# rc_rx_3_3V_with_gyro_iface_and_rear_H-br.net
KiCad netlist of a schematic drawn in EAGLE
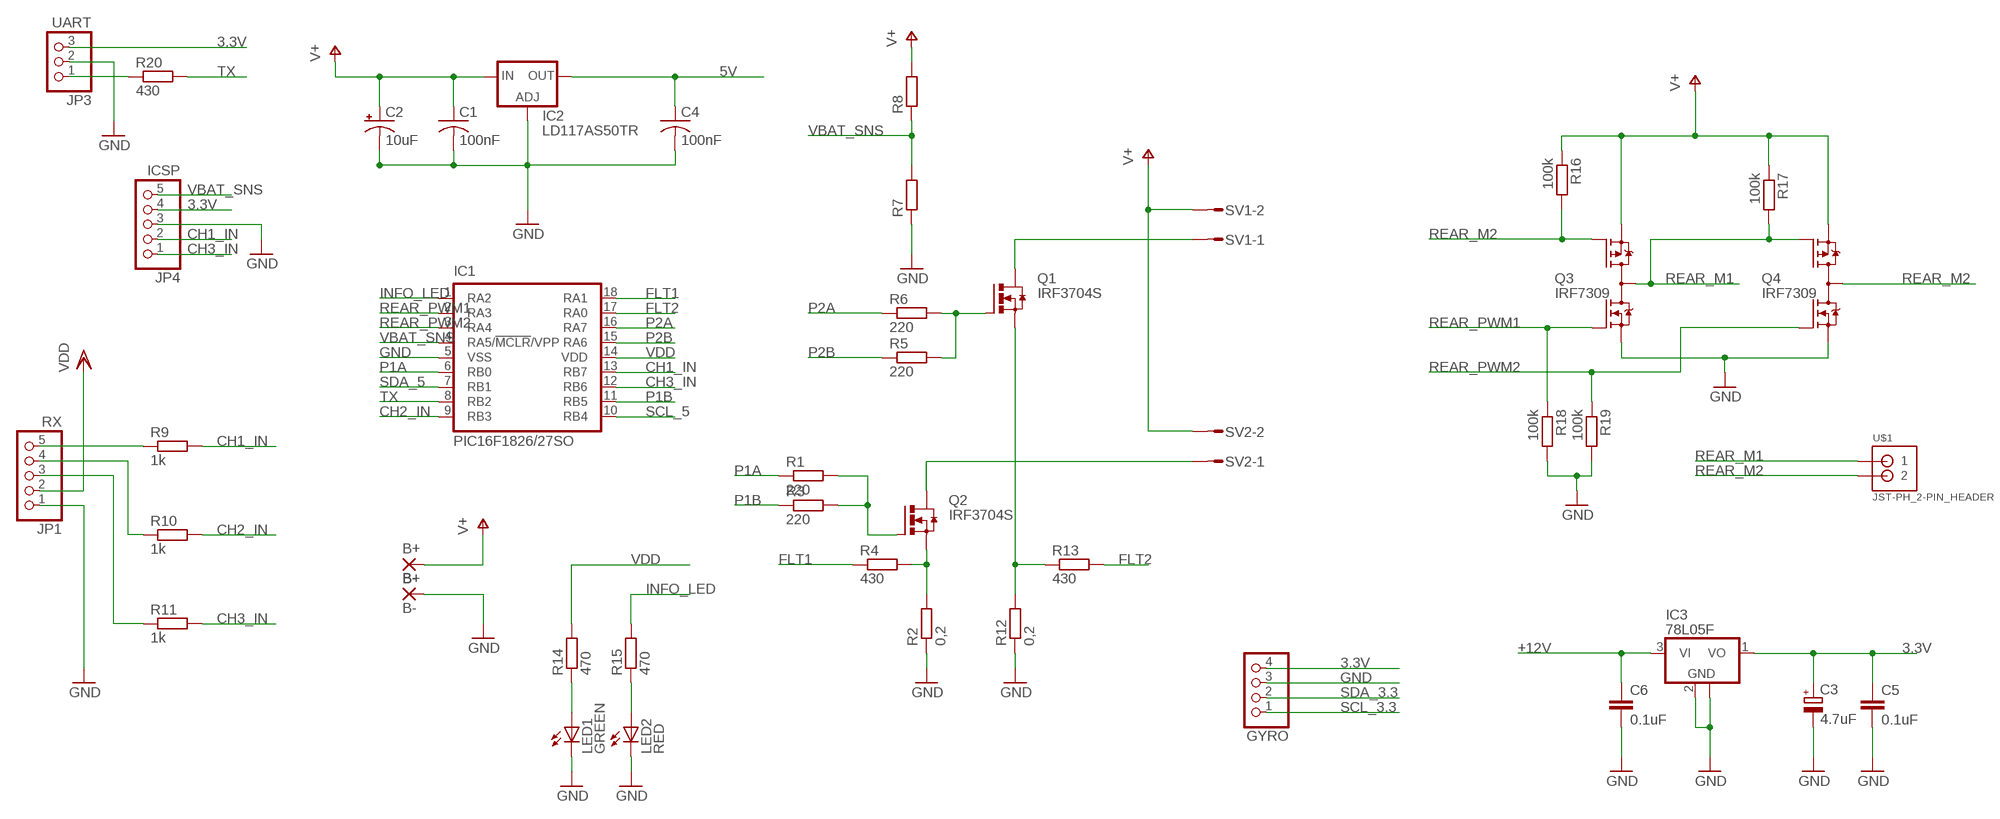
[diagram p0: schematic, sheet 1]

(export (version "E")
  (design (tool "Eeschema 10.0.6"))
  (components
    (comp (ref "B+")
      (value "B+")
      (footprint "eagle-import:3,81_1,4")
      (libsource (lib "eagle-import") (part "3,81/1,4"))
    )
    (comp (ref "B-")
      (value "B-")
      (footprint "eagle-import:3,81_1,4")
      (libsource (lib "eagle-import") (part "3,81/1,4"))
    )
    (comp (ref "C1")
      (value "100nF")
      (footprint "eagle-import:C0805")
      (libsource (lib "eagle-import") (part "C-USC0805"))
    )
    (comp (ref "C2")
      (value "10uF")
      (footprint "eagle-import:E3,5-8")
      (libsource (lib "eagle-import") (part "CPOL-USE3.5-8"))
    )
    (comp (ref "C3")
      (value "4.7uF")
      (footprint "eagle-import:E1,8-4")
      (libsource (lib "eagle-import") (part "CPOL-EUE1.8-4"))
    )
    (comp (ref "C4")
      (value "100nF")
      (footprint "eagle-import:C0805")
      (libsource (lib "eagle-import") (part "C-USC0805"))
    )
    (comp (ref "C5")
      (value "0.1uF")
      (footprint "eagle-import:C0805")
      (libsource (lib "eagle-import") (part "C-EUC0805"))
    )
    (comp (ref "C6")
      (value "0.1uF")
      (footprint "eagle-import:C0805")
      (libsource (lib "eagle-import") (part "C-EUC0805"))
    )
    (comp (ref "GYRO")
      (value "PINHD-1X4")
      (footprint "eagle-import:1X04")
      (libsource (lib "eagle-import") (part "PINHD-1X4"))
    )
    (comp (ref "IC1")
      (value "PIC16F1826/27SO")
      (footprint "eagle-import:SO-18W")
      (libsource (lib "eagle-import") (part "PIC16F1826/27SO"))
    )
    (comp (ref "IC2")
      (value "LD117AS50TR")
      (footprint "eagle-import:SOT223")
      (libsource (lib "eagle-import") (part "LD117A?S50TR"))
    )
    (comp (ref "IC3")
      (value "78L05F")
      (footprint "eagle-import:SOT89")
      (libsource (lib "eagle-import") (part "78LF05"))
    )
    (comp (ref "JP1")
      (value "RX")
      (footprint "eagle-import:1X05")
      (libsource (lib "eagle-import") (part "PINHD-1X5"))
    )
    (comp (ref "JP3")
      (value "UART")
      (footprint "eagle-import:1X03")
      (libsource (lib "eagle-import") (part "PINHD-1X3"))
    )
    (comp (ref "JP4")
      (value "ICSP")
      (footprint "eagle-import:1X05")
      (libsource (lib "eagle-import") (part "PINHD-1X5"))
    )
    (comp (ref "LED1")
      (value "GREEN")
      (footprint "eagle-import:CHIP-LED0603")
      (libsource (lib "eagle-import") (part "LEDCHIP-LED0603"))
    )
    (comp (ref "LED2")
      (value "RED")
      (footprint "eagle-import:CHIP-LED0603")
      (libsource (lib "eagle-import") (part "LEDCHIP-LED0603"))
    )
    (comp (ref "Q1")
      (value "IRF3704S")
      (footprint "eagle-import:D2PACK")
      (libsource (lib "eagle-import") (part "IRF3704S"))
    )
    (comp (ref "Q2")
      (value "IRF3704S")
      (footprint "eagle-import:D2PACK")
      (libsource (lib "eagle-import") (part "IRF3704S"))
    )
    (comp (ref "Q3")
      (value "IRF7309")
      (footprint "eagle-import:SO08-IRF")
      (libsource (lib "eagle-import") (part "IRF7389"))
    )
    (comp (ref "Q4")
      (value "IRF7309")
      (footprint "eagle-import:SO08-IRF")
      (libsource (lib "eagle-import") (part "IRF7389"))
    )
    (comp (ref "R1")
      (value "220")
      (footprint "eagle-import:M0805")
      (libsource (lib "eagle-import") (part "R-EU_M0805"))
    )
    (comp (ref "R2")
      (value "0,2")
      (footprint "eagle-import:M0805")
      (libsource (lib "eagle-import") (part "R-EU_M0805"))
    )
    (comp (ref "R3")
      (value "220")
      (footprint "eagle-import:M0805")
      (libsource (lib "eagle-import") (part "R-EU_M0805"))
    )
    (comp (ref "R4")
      (value "430")
      (footprint "eagle-import:M0805")
      (libsource (lib "eagle-import") (part "R-EU_M0805"))
    )
    (comp (ref "R5")
      (value "220")
      (footprint "eagle-import:R0805")
      (libsource (lib "eagle-import") (part "R-EU_R0805"))
    )
    (comp (ref "R6")
      (value "220")
      (footprint "eagle-import:M0805")
      (libsource (lib "eagle-import") (part "R-EU_M0805"))
    )
    (comp (ref "R7")
      (value "R-EU_R0805")
      (footprint "eagle-import:R0805")
      (libsource (lib "eagle-import") (part "R-EU_R0805"))
    )
    (comp (ref "R8")
      (value "R-EU_R0805")
      (footprint "eagle-import:R0805")
      (libsource (lib "eagle-import") (part "R-EU_R0805"))
    )
    (comp (ref "R9")
      (value "1k")
      (footprint "eagle-import:M0805")
      (libsource (lib "eagle-import") (part "R-EU_M0805"))
    )
    (comp (ref "R10")
      (value "1k")
      (footprint "eagle-import:M0805")
      (libsource (lib "eagle-import") (part "R-EU_M0805"))
    )
    (comp (ref "R11")
      (value "1k")
      (footprint "eagle-import:M0805")
      (libsource (lib "eagle-import") (part "R-EU_M0805"))
    )
    (comp (ref "R12")
      (value "0,2")
      (footprint "eagle-import:M0805")
      (libsource (lib "eagle-import") (part "R-EU_M0805"))
    )
    (comp (ref "R13")
      (value "430")
      (footprint "eagle-import:M0805")
      (libsource (lib "eagle-import") (part "R-EU_M0805"))
    )
    (comp (ref "R14")
      (value "470")
      (footprint "eagle-import:M0805")
      (libsource (lib "eagle-import") (part "R-EU_M0805"))
    )
    (comp (ref "R15")
      (value "470")
      (footprint "eagle-import:M0805")
      (libsource (lib "eagle-import") (part "R-EU_M0805"))
    )
    (comp (ref "R16")
      (value "100k")
      (footprint "eagle-import:M0805")
      (libsource (lib "eagle-import") (part "R-EU_M0805"))
    )
    (comp (ref "R17")
      (value "100k")
      (footprint "eagle-import:M0805")
      (libsource (lib "eagle-import") (part "R-EU_M0805"))
    )
    (comp (ref "R18")
      (value "100k")
      (footprint "eagle-import:M0805")
      (libsource (lib "eagle-import") (part "R-EU_M0805"))
    )
    (comp (ref "R19")
      (value "100k")
      (footprint "eagle-import:M0805")
      (libsource (lib "eagle-import") (part "R-EU_M0805"))
    )
    (comp (ref "R20")
      (value "430")
      (footprint "eagle-import:M0805")
      (libsource (lib "eagle-import") (part "R-EU_M0805"))
    )
    (comp (ref "SV1")
      (value "S02P")
      (footprint "eagle-import:S02P")
      (libsource (lib "eagle-import") (part "S02P"))
    )
    (comp (ref "SV2")
      (value "S02P")
      (footprint "eagle-import:S02P")
      (libsource (lib "eagle-import") (part "S02P"))
    )
    (comp (ref "U$1")
      (value "JST-PH_2-PIN_HEADER")
      (footprint "eagle-import:JST_B2B-PH_HEADER")
      (libsource (lib "eagle-import") (part "JST-PH_2-PIN_HEADER"))
    )
  )
  (nets
    (net (code "1") (name "/+12V") (class "Default")
      (node (ref "C6") (pin "1") (pinfunction "1_1") (pintype "passive"))
      (node (ref "IC3") (pin "3") (pinfunction "VI_3") (pintype "input"))
    )
    (net (code "2") (name "/3.3V") (class "Default")
      (node (ref "C3") (pin "+") (pinfunction "+_+") (pintype "passive"))
      (node (ref "C5") (pin "1") (pinfunction "1_1") (pintype "passive"))
      (node (ref "GYRO") (pin "4") (pinfunction "4_4") (pintype "passive"))
      (node (ref "IC3") (pin "1") (pinfunction "VO_1") (pintype "passive"))
      (node (ref "JP3") (pin "3") (pinfunction "3_3") (pintype "passive"))
      (node (ref "JP4") (pin "4") (pinfunction "4_4") (pintype "passive"))
    )
    (net (code "3") (name "/5V") (class "Default")
      (node (ref "C4") (pin "1") (pinfunction "1_1") (pintype "passive"))
      (node (ref "IC2") (pin "4") (pinfunction "OUT_4") (pintype "passive"))
    )
    (net (code "4") (name "/CH1_IN") (class "Default")
      (node (ref "IC1") (pin "13") (pinfunction "RB7_13") (pintype "bidirectional"))
      (node (ref "JP4") (pin "2") (pinfunction "2_2") (pintype "passive"))
      (node (ref "R9") (pin "2") (pinfunction "2_2") (pintype "passive"))
    )
    (net (code "5") (name "/CH2_IN") (class "Default")
      (node (ref "IC1") (pin "9") (pinfunction "RB3_9") (pintype "bidirectional"))
      (node (ref "R10") (pin "2") (pinfunction "2_2") (pintype "passive"))
    )
    (net (code "6") (name "/CH3_IN") (class "Default")
      (node (ref "IC1") (pin "12") (pinfunction "RB6_12") (pintype "bidirectional"))
      (node (ref "JP4") (pin "1") (pinfunction "1_1") (pintype "passive"))
      (node (ref "R11") (pin "2") (pinfunction "2_2") (pintype "passive"))
    )
    (net (code "7") (name "/FLT1") (class "Default")
      (node (ref "IC1") (pin "18") (pinfunction "RA1_18") (pintype "bidirectional"))
      (node (ref "R4") (pin "1") (pinfunction "1_1") (pintype "passive"))
    )
    (net (code "8") (name "/FLT2") (class "Default")
      (node (ref "IC1") (pin "17") (pinfunction "RA0_17") (pintype "bidirectional"))
      (node (ref "R13") (pin "2") (pinfunction "2_2") (pintype "passive"))
    )
    (net (code "9") (name "/INFO_LED") (class "Default")
      (node (ref "IC1") (pin "1") (pinfunction "RA2_1") (pintype "bidirectional"))
      (node (ref "R15") (pin "2") (pinfunction "2_2") (pintype "passive"))
    )
    (net (code "10") (name "/P1A") (class "Default")
      (node (ref "IC1") (pin "6") (pinfunction "RB0_6") (pintype "bidirectional"))
      (node (ref "R1") (pin "1") (pinfunction "1_1") (pintype "passive"))
    )
    (net (code "11") (name "/P1B") (class "Default")
      (node (ref "IC1") (pin "11") (pinfunction "RB5_11") (pintype "bidirectional"))
      (node (ref "R3") (pin "1") (pinfunction "1_1") (pintype "passive"))
    )
    (net (code "12") (name "/P2A") (class "Default")
      (node (ref "IC1") (pin "16") (pinfunction "RA7_16") (pintype "bidirectional"))
      (node (ref "R6") (pin "1") (pinfunction "1_1") (pintype "passive"))
    )
    (net (code "13") (name "/P2B") (class "Default")
      (node (ref "IC1") (pin "15") (pinfunction "RA6_15") (pintype "bidirectional"))
      (node (ref "R5") (pin "1") (pinfunction "1_1") (pintype "passive"))
    )
    (net (code "14") (name "/REAR_M1") (class "Default")
      (node (ref "Q3") (pin "5") (pinfunction "D_5") (pintype "passive"))
      (node (ref "Q3") (pin "6") (pinfunction "D_6") (pintype "passive"))
      (node (ref "Q3") (pin "7") (pinfunction "D_7") (pintype "passive"))
      (node (ref "Q3") (pin "8") (pinfunction "D_8") (pintype "passive"))
      (node (ref "Q4") (pin "4") (pinfunction "P-G_4") (pintype "passive"))
      (node (ref "R17") (pin "2") (pinfunction "2_2") (pintype "passive"))
      (node (ref "U$1") (pin "P1") (pinfunction "1_P1") (pintype "bidirectional"))
    )
    (net (code "15") (name "/REAR_M2") (class "Default")
      (node (ref "Q3") (pin "4") (pinfunction "P-G_4") (pintype "passive"))
      (node (ref "Q4") (pin "5") (pinfunction "D_5") (pintype "passive"))
      (node (ref "Q4") (pin "6") (pinfunction "D_6") (pintype "passive"))
      (node (ref "Q4") (pin "7") (pinfunction "D_7") (pintype "passive"))
      (node (ref "Q4") (pin "8") (pinfunction "D_8") (pintype "passive"))
      (node (ref "R16") (pin "2") (pinfunction "2_2") (pintype "passive"))
      (node (ref "U$1") (pin "P2") (pinfunction "2_P2") (pintype "bidirectional"))
    )
    (net (code "16") (name "/REAR_PWM1") (class "Default")
      (node (ref "IC1") (pin "2") (pinfunction "RA3_2") (pintype "bidirectional"))
      (node (ref "Q3") (pin "2") (pinfunction "N-G_2") (pintype "passive"))
      (node (ref "R18") (pin "1") (pinfunction "1_1") (pintype "passive"))
    )
    (net (code "17") (name "/REAR_PWM2") (class "Default")
      (node (ref "IC1") (pin "3") (pinfunction "RA4_3") (pintype "bidirectional"))
      (node (ref "Q4") (pin "2") (pinfunction "N-G_2") (pintype "passive"))
      (node (ref "R19") (pin "1") (pinfunction "1_1") (pintype "passive"))
    )
    (net (code "18") (name "/SCL_3.3") (class "Default")
      (node (ref "GYRO") (pin "1") (pinfunction "1_1") (pintype "passive"))
    )
    (net (code "19") (name "/SCL_5") (class "Default")
      (node (ref "IC1") (pin "10") (pinfunction "RB4_10") (pintype "bidirectional"))
    )
    (net (code "20") (name "/SDA_3.3") (class "Default")
      (node (ref "GYRO") (pin "2") (pinfunction "2_2") (pintype "passive"))
    )
    (net (code "21") (name "/SDA_5") (class "Default")
      (node (ref "IC1") (pin "7") (pinfunction "RB1_7") (pintype "bidirectional"))
    )
    (net (code "22") (name "/TX") (class "Default")
      (node (ref "IC1") (pin "8") (pinfunction "RB2_8") (pintype "bidirectional"))
      (node (ref "R20") (pin "2") (pinfunction "2_2") (pintype "passive"))
    )
    (net (code "23") (name "/VBAT_SNS") (class "Default")
      (node (ref "IC1") (pin "4") (pinfunction "RA5/~{MCLR}/VPP_4") (pintype "bidirectional"))
      (node (ref "JP4") (pin "5") (pinfunction "5_5") (pintype "passive"))
      (node (ref "R7") (pin "2") (pinfunction "2_2") (pintype "passive"))
      (node (ref "R8") (pin "1") (pinfunction "1_1") (pintype "passive"))
    )
    (net (code "24") (name "GND") (class "Default")
      (node (ref "B-") (pin "1") (pinfunction "P_1") (pintype "passive"))
      (node (ref "C1") (pin "2") (pinfunction "2_2") (pintype "passive"))
      (node (ref "C2") (pin "-") (pinfunction "-_-") (pintype "passive"))
      (node (ref "C3") (pin "-") (pinfunction "-_-") (pintype "passive"))
      (node (ref "C4") (pin "2") (pinfunction "2_2") (pintype "passive"))
      (node (ref "C5") (pin "2") (pinfunction "2_2") (pintype "passive"))
      (node (ref "C6") (pin "2") (pinfunction "2_2") (pintype "passive"))
      (node (ref "GYRO") (pin "3") (pinfunction "3_3") (pintype "passive"))
      (node (ref "IC1") (pin "5") (pinfunction "VSS_5") (pintype "power_in"))
      (node (ref "IC2") (pin "1") (pinfunction "ADJ_1") (pintype "input"))
      (node (ref "IC3") (pin "2") (pinfunction "GND_2") (pintype "passive"))
      (node (ref "IC3") (pin "2@1") (pinfunction "GND_2@1") (pintype "passive"))
      (node (ref "JP1") (pin "1") (pinfunction "1_1") (pintype "passive"))
      (node (ref "JP3") (pin "2") (pinfunction "2_2") (pintype "passive"))
      (node (ref "JP4") (pin "3") (pinfunction "3_3") (pintype "passive"))
      (node (ref "LED1") (pin "C") (pinfunction "C_C") (pintype "passive"))
      (node (ref "LED2") (pin "C") (pinfunction "C_C") (pintype "passive"))
      (node (ref "Q3") (pin "1") (pinfunction "N-S_1") (pintype "passive"))
      (node (ref "Q4") (pin "1") (pinfunction "N-S_1") (pintype "passive"))
      (node (ref "R12") (pin "1") (pinfunction "1_1") (pintype "passive"))
      (node (ref "R18") (pin "2") (pinfunction "2_2") (pintype "passive"))
      (node (ref "R19") (pin "2") (pinfunction "2_2") (pintype "passive"))
      (node (ref "R2") (pin "1") (pinfunction "1_1") (pintype "passive"))
      (node (ref "R7") (pin "1") (pinfunction "1_1") (pintype "passive"))
    )
    (net (code "25") (name "Net-(JP1-Pad3)") (class "Default")
      (node (ref "JP1") (pin "3") (pinfunction "3_3") (pintype "passive"))
      (node (ref "R11") (pin "1") (pinfunction "1_1") (pintype "passive"))
    )
    (net (code "26") (name "Net-(JP1-Pad4)") (class "Default")
      (node (ref "JP1") (pin "4") (pinfunction "4_4") (pintype "passive"))
      (node (ref "R10") (pin "1") (pinfunction "1_1") (pintype "passive"))
    )
    (net (code "27") (name "Net-(JP1-Pad5)") (class "Default")
      (node (ref "JP1") (pin "5") (pinfunction "5_5") (pintype "passive"))
      (node (ref "R9") (pin "1") (pinfunction "1_1") (pintype "passive"))
    )
    (net (code "28") (name "Net-(JP3-Pad1)") (class "Default")
      (node (ref "JP3") (pin "1") (pinfunction "1_1") (pintype "passive"))
      (node (ref "R20") (pin "1") (pinfunction "1_1") (pintype "passive"))
    )
    (net (code "29") (name "Net-(LED1-PadA)") (class "Default")
      (node (ref "LED1") (pin "A") (pinfunction "A_A") (pintype "passive"))
      (node (ref "R14") (pin "1") (pinfunction "1_1") (pintype "passive"))
    )
    (net (code "30") (name "Net-(LED2-PadA)") (class "Default")
      (node (ref "LED2") (pin "A") (pinfunction "A_A") (pintype "passive"))
      (node (ref "R15") (pin "1") (pinfunction "1_1") (pintype "passive"))
    )
    (net (code "31") (name "Net-(Q1-D)") (class "Default")
      (node (ref "Q1") (pin "2") (pinfunction "D_2") (pintype "passive"))
      (node (ref "SV1") (pin "1") (pinfunction "S_1") (pintype "passive"))
    )
    (net (code "32") (name "Net-(Q1-G)") (class "Default")
      (node (ref "Q1") (pin "1") (pinfunction "G_1") (pintype "passive"))
      (node (ref "R5") (pin "2") (pinfunction "2_2") (pintype "passive"))
      (node (ref "R6") (pin "2") (pinfunction "2_2") (pintype "passive"))
    )
    (net (code "33") (name "Net-(Q1-S)") (class "Default")
      (node (ref "Q1") (pin "3") (pinfunction "S_3") (pintype "passive"))
      (node (ref "R12") (pin "2") (pinfunction "2_2") (pintype "passive"))
      (node (ref "R13") (pin "1") (pinfunction "1_1") (pintype "passive"))
    )
    (net (code "34") (name "Net-(Q2-D)") (class "Default")
      (node (ref "Q2") (pin "2") (pinfunction "D_2") (pintype "passive"))
      (node (ref "SV2") (pin "1") (pinfunction "S_1") (pintype "passive"))
    )
    (net (code "35") (name "Net-(Q2-G)") (class "Default")
      (node (ref "Q2") (pin "1") (pinfunction "G_1") (pintype "passive"))
      (node (ref "R1") (pin "2") (pinfunction "2_2") (pintype "passive"))
      (node (ref "R3") (pin "2") (pinfunction "2_2") (pintype "passive"))
    )
    (net (code "36") (name "Net-(Q2-S)") (class "Default")
      (node (ref "Q2") (pin "3") (pinfunction "S_3") (pintype "passive"))
      (node (ref "R2") (pin "2") (pinfunction "2_2") (pintype "passive"))
      (node (ref "R4") (pin "2") (pinfunction "2_2") (pintype "passive"))
    )
    (net (code "37") (name "V+") (class "Default")
      (node (ref "B+") (pin "1") (pinfunction "P_1") (pintype "passive"))
      (node (ref "C1") (pin "1") (pinfunction "1_1") (pintype "passive"))
      (node (ref "C2") (pin "+") (pinfunction "+_+") (pintype "passive"))
      (node (ref "IC2") (pin "3") (pinfunction "IN_3") (pintype "input"))
      (node (ref "Q3") (pin "3") (pinfunction "P-S_3") (pintype "passive"))
      (node (ref "Q4") (pin "3") (pinfunction "P-S_3") (pintype "passive"))
      (node (ref "R16") (pin "1") (pinfunction "1_1") (pintype "passive"))
      (node (ref "R17") (pin "1") (pinfunction "1_1") (pintype "passive"))
      (node (ref "R8") (pin "2") (pinfunction "2_2") (pintype "passive"))
      (node (ref "SV1") (pin "2") (pinfunction "S_2") (pintype "passive"))
      (node (ref "SV2") (pin "2") (pinfunction "S_2") (pintype "passive"))
    )
    (net (code "38") (name "VDD") (class "Default")
      (node (ref "IC1") (pin "14") (pinfunction "VDD_14") (pintype "power_in"))
      (node (ref "JP1") (pin "2") (pinfunction "2_2") (pintype "passive"))
      (node (ref "R14") (pin "2") (pinfunction "2_2") (pintype "passive"))
    )
  )
)
